# Raspberry_Pi4.net
KiCad netlist of a schematic drawn in Altium Designer
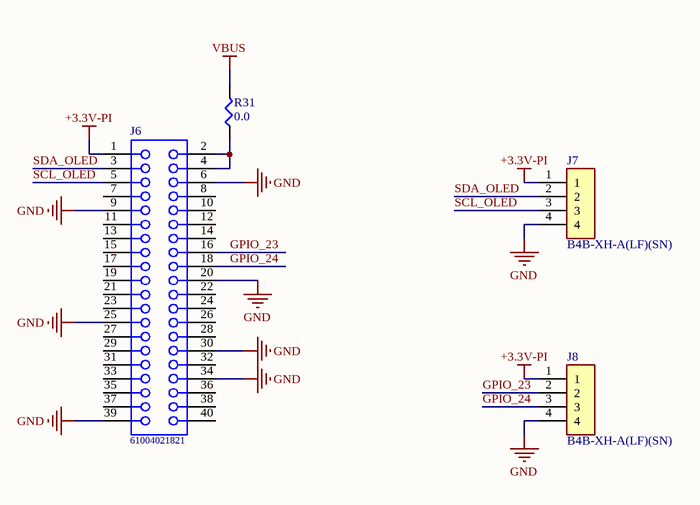
[diagram p0: Raspberry_Pi4.SchDoc]

(export (version "E")
  (design (tool "Eeschema 10.0.6"))
  (components
    (comp (ref "J6")
      (value "61004021821")
      (footprint "61004021821")
      (description "WR-PHD Socket Header, SMT, pitch 2.54mm, Dual Row, Vertical, 40p")
      (fields (field (name "MANUFACTURER") "Wurth Elektronik"))
      (libsource (lib "Altium_WR-PHD (rev20a)") (part "61004021821"))
    )
    (comp (ref "J7")
      (value "B4B-XH-A(LF)(SN)")
      (footprint "JST_B4B-XH-A(LF)(SN)")
      (description "Connector Header Through Hole 4 position 0.098 (2.50mm)")
      (fields (field (name "MF") "JST Sales"))
      (libsource (lib "B4B-XH-A_LF__SN_") (part "B4B-XH-A(LF)(SN)"))
    )
    (comp (ref "J8")
      (value "B4B-XH-A(LF)(SN)")
      (footprint "JST_B4B-XH-A(LF)(SN)")
      (description "Connector Header Through Hole 4 position 0.098 (2.50mm)")
      (fields (field (name "MF") "JST Sales"))
      (libsource (lib "B4B-XH-A_LF__SN_") (part "B4B-XH-A(LF)(SN)"))
    )
    (comp (ref "R31")
      (value "0.0")
      (footprint "SMD-0402-RES")
      (description "RES SMD 0.0OHM JUMPER 1/10W 0402")
      (fields (field (name "PART NUMBER") "ERJ-2GE0R00X") (field (name "DIGI-KEY PART NUMBER") "P0.0JCT-ND"))
      (libsource (lib "res_panasonic_erj_xls") (part "RESISTOR"))
    )
  )
  (nets
    (net (code "1") (name "+3.3V-PI") (class "Default")
      (node (ref "J6") (pin "1") (pinfunction "1_1") (pintype "passive"))
      (node (ref "J7") (pin "1") (pinfunction "1_1") (pintype "passive"))
      (node (ref "J8") (pin "1") (pinfunction "1_1") (pintype "passive"))
    )
    (net (code "2") (name "/GPIO_23") (class "Default")
      (node (ref "J6") (pin "16") (pinfunction "16_16") (pintype "passive"))
      (node (ref "J8") (pin "2") (pinfunction "2_2") (pintype "passive"))
    )
    (net (code "3") (name "/GPIO_24") (class "Default")
      (node (ref "J6") (pin "18") (pinfunction "18_18") (pintype "passive"))
      (node (ref "J8") (pin "3") (pinfunction "3_3") (pintype "passive"))
    )
    (net (code "4") (name "/SCL_OLED") (class "Default")
      (node (ref "J6") (pin "5") (pinfunction "5_5") (pintype "passive"))
      (node (ref "J7") (pin "3") (pinfunction "3_3") (pintype "passive"))
    )
    (net (code "5") (name "/SDA_OLED") (class "Default")
      (node (ref "J6") (pin "3") (pinfunction "3_3") (pintype "passive"))
      (node (ref "J7") (pin "2") (pinfunction "2_2") (pintype "passive"))
    )
    (net (code "6") (name "GND") (class "Default")
      (node (ref "J6") (pin "20") (pinfunction "20_20") (pintype "passive"))
      (node (ref "J6") (pin "25") (pinfunction "25_25") (pintype "passive"))
      (node (ref "J6") (pin "30") (pinfunction "30_30") (pintype "passive"))
      (node (ref "J6") (pin "34") (pinfunction "34_34") (pintype "passive"))
      (node (ref "J6") (pin "39") (pinfunction "39_39") (pintype "passive"))
      (node (ref "J6") (pin "6") (pinfunction "6_6") (pintype "passive"))
      (node (ref "J6") (pin "9") (pinfunction "9_9") (pintype "passive"))
      (node (ref "J7") (pin "4") (pinfunction "4_4") (pintype "passive"))
      (node (ref "J8") (pin "4") (pinfunction "4_4") (pintype "passive"))
    )
    (net (code "7") (name "Net-(J6-Pad2)") (class "Default")
      (node (ref "J6") (pin "2") (pinfunction "2_2") (pintype "passive"))
      (node (ref "J6") (pin "4") (pinfunction "4_4") (pintype "passive"))
      (node (ref "R31") (pin "1") (pinfunction "1_1") (pintype "passive"))
    )
    (net (code "8") (name "VBUS") (class "Default")
      (node (ref "R31") (pin "2") (pinfunction "2_2") (pintype "passive"))
    )
    (net (code "9") (name "unconnected-(J6-Pad7)") (class "Default")
      (node (ref "J6") (pin "7") (pinfunction "7_7") (pintype "passive"))
    )
    (net (code "10") (name "unconnected-(J6-Pad8)") (class "Default")
      (node (ref "J6") (pin "8") (pinfunction "8_8") (pintype "passive"))
    )
    (net (code "11") (name "unconnected-(J6-Pad10)") (class "Default")
      (node (ref "J6") (pin "10") (pinfunction "10_10") (pintype "passive"))
    )
    (net (code "12") (name "unconnected-(J6-Pad11)") (class "Default")
      (node (ref "J6") (pin "11") (pinfunction "11_11") (pintype "passive"))
    )
    (net (code "13") (name "unconnected-(J6-Pad12)") (class "Default")
      (node (ref "J6") (pin "12") (pinfunction "12_12") (pintype "passive"))
    )
    (net (code "14") (name "unconnected-(J6-Pad13)") (class "Default")
      (node (ref "J6") (pin "13") (pinfunction "13_13") (pintype "passive"))
    )
    (net (code "15") (name "unconnected-(J6-Pad14)") (class "Default")
      (node (ref "J6") (pin "14") (pinfunction "14_14") (pintype "passive"))
    )
    (net (code "16") (name "unconnected-(J6-Pad15)") (class "Default")
      (node (ref "J6") (pin "15") (pinfunction "15_15") (pintype "passive"))
    )
    (net (code "17") (name "unconnected-(J6-Pad17)") (class "Default")
      (node (ref "J6") (pin "17") (pinfunction "17_17") (pintype "passive"))
    )
    (net (code "18") (name "unconnected-(J6-Pad19)") (class "Default")
      (node (ref "J6") (pin "19") (pinfunction "19_19") (pintype "passive"))
    )
    (net (code "19") (name "unconnected-(J6-Pad21)") (class "Default")
      (node (ref "J6") (pin "21") (pinfunction "21_21") (pintype "passive"))
    )
    (net (code "20") (name "unconnected-(J6-Pad22)") (class "Default")
      (node (ref "J6") (pin "22") (pinfunction "22_22") (pintype "passive"))
    )
    (net (code "21") (name "unconnected-(J6-Pad23)") (class "Default")
      (node (ref "J6") (pin "23") (pinfunction "23_23") (pintype "passive"))
    )
    (net (code "22") (name "unconnected-(J6-Pad24)") (class "Default")
      (node (ref "J6") (pin "24") (pinfunction "24_24") (pintype "passive"))
    )
    (net (code "23") (name "unconnected-(J6-Pad26)") (class "Default")
      (node (ref "J6") (pin "26") (pinfunction "26_26") (pintype "passive"))
    )
    (net (code "24") (name "unconnected-(J6-Pad27)") (class "Default")
      (node (ref "J6") (pin "27") (pinfunction "27_27") (pintype "passive"))
    )
    (net (code "25") (name "unconnected-(J6-Pad28)") (class "Default")
      (node (ref "J6") (pin "28") (pinfunction "28_28") (pintype "passive"))
    )
    (net (code "26") (name "unconnected-(J6-Pad29)") (class "Default")
      (node (ref "J6") (pin "29") (pinfunction "29_29") (pintype "passive"))
    )
    (net (code "27") (name "unconnected-(J6-Pad31)") (class "Default")
      (node (ref "J6") (pin "31") (pinfunction "31_31") (pintype "passive"))
    )
    (net (code "28") (name "unconnected-(J6-Pad32)") (class "Default")
      (node (ref "J6") (pin "32") (pinfunction "32_32") (pintype "passive"))
    )
    (net (code "29") (name "unconnected-(J6-Pad33)") (class "Default")
      (node (ref "J6") (pin "33") (pinfunction "33_33") (pintype "passive"))
    )
    (net (code "30") (name "unconnected-(J6-Pad35)") (class "Default")
      (node (ref "J6") (pin "35") (pinfunction "35_35") (pintype "passive"))
    )
    (net (code "31") (name "unconnected-(J6-Pad36)") (class "Default")
      (node (ref "J6") (pin "36") (pinfunction "36_36") (pintype "passive"))
    )
    (net (code "32") (name "unconnected-(J6-Pad37)") (class "Default")
      (node (ref "J6") (pin "37") (pinfunction "37_37") (pintype "passive"))
    )
    (net (code "33") (name "unconnected-(J6-Pad38)") (class "Default")
      (node (ref "J6") (pin "38") (pinfunction "38_38") (pintype "passive"))
    )
    (net (code "34") (name "unconnected-(J6-Pad40)") (class "Default")
      (node (ref "J6") (pin "40") (pinfunction "40_40") (pintype "passive"))
    )
  )
)
